# Camera_module.net
KiCad netlist of a schematic drawn in Altium Designer
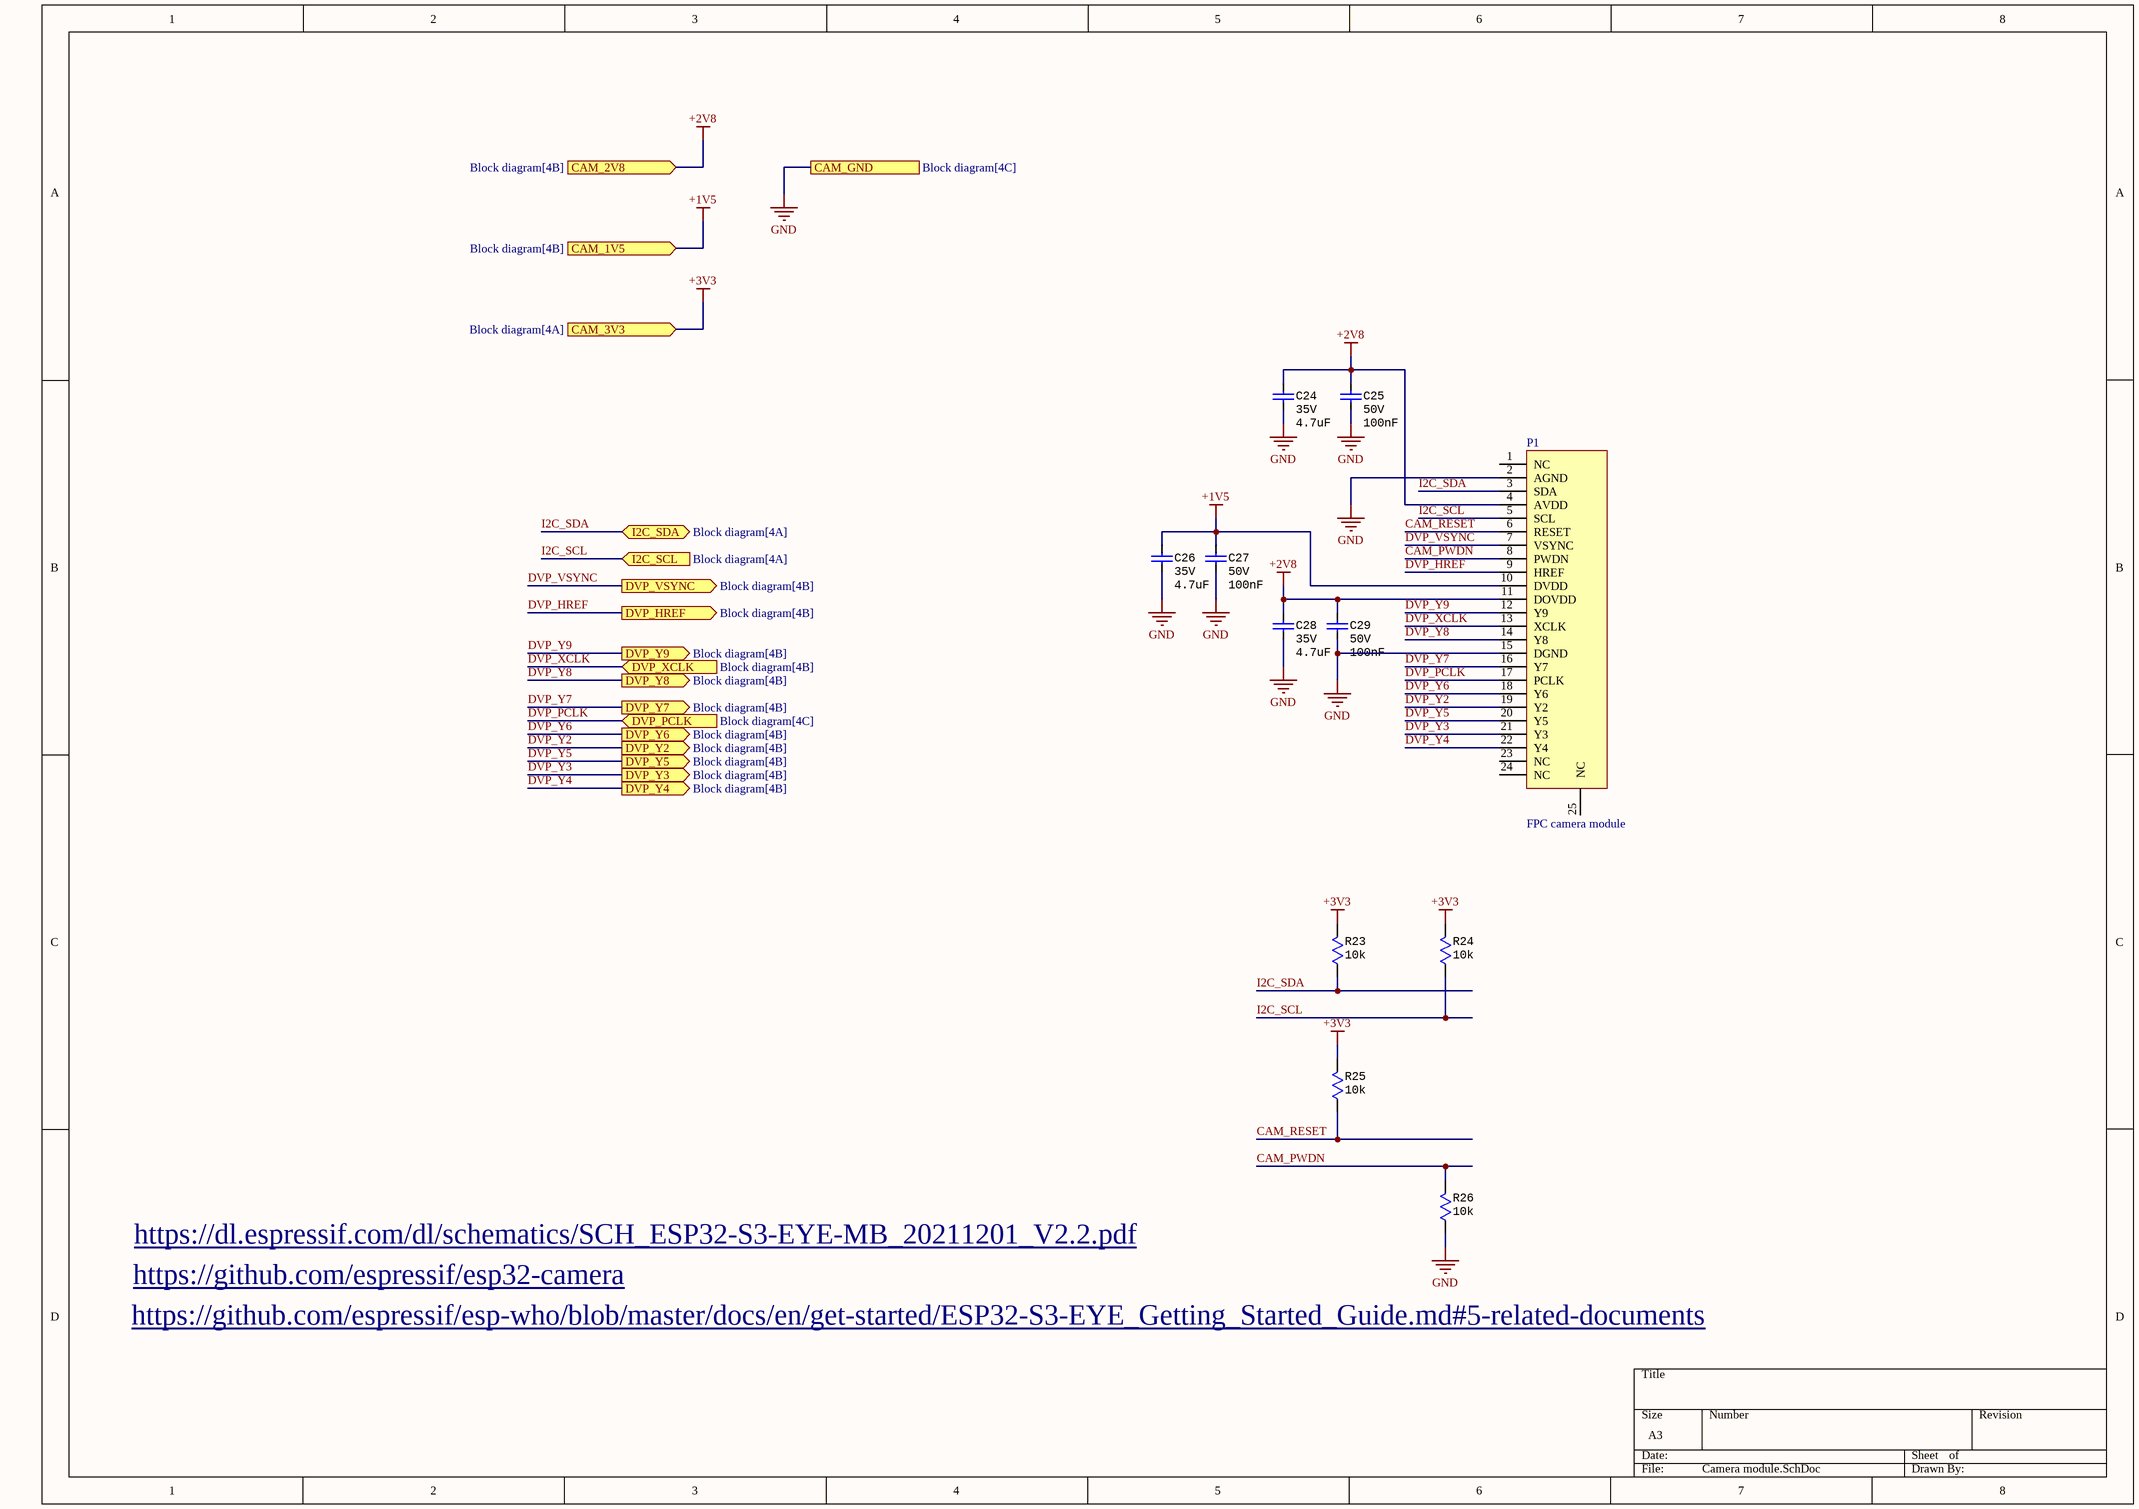
[diagram p0: Camera module.SchDoc]

(export (version "E")
  (design (tool "Eeschema 10.0.6"))
  (components
    (comp (ref "C24")
      (value "4.7uF")
      (footprint "CAP Ceramic SMD 0603")
      (description "Multilayer Ceramic Capacitor, 4.7 uF, 35 V, ± 10%, X5R, 0603 [1608 Metric]")
      (fields
        (field (name "MANUFACTURER") "Murata")
        (field (name "MANUFACTURER PART NUMBER") "GRM188R6YA475KE15D")
        (field (name "VOLTAGE") "35V")
      )
      (libsource (lib "Passive") (part "CAP 0603 4.7uF 35V"))
    )
    (comp (ref "C25")
      (value "100nF")
      (footprint "CAP Ceramic SMD 0603")
      (description "Multilayer Ceramic Capacitors MLCC Surface Mount 0603 0.1uF 50 Volts X7R 10%")
      (fields
        (field (name "MANUFACTURER") "Murata")
        (field (name "MANUFACTURER PART NUMBER") "GRM188R71H104KA93D")
        (field (name "VOLTAGE") "50V")
      )
      (libsource (lib "Passive") (part "CAP 0603 100nF 50V"))
    )
    (comp (ref "C26")
      (value "4.7uF")
      (footprint "CAP Ceramic SMD 0603")
      (description "Multilayer Ceramic Capacitor, 4.7 uF, 35 V, ± 10%, X5R, 0603 [1608 Metric]")
      (fields
        (field (name "MANUFACTURER") "Murata")
        (field (name "MANUFACTURER PART NUMBER") "GRM188R6YA475KE15D")
        (field (name "VOLTAGE") "35V")
      )
      (libsource (lib "Passive") (part "CAP 0603 4.7uF 35V"))
    )
    (comp (ref "C27")
      (value "100nF")
      (footprint "CAP Ceramic SMD 0603")
      (description "Multilayer Ceramic Capacitors MLCC Surface Mount 0603 0.1uF 50 Volts X7R 10%")
      (fields
        (field (name "MANUFACTURER") "Murata")
        (field (name "MANUFACTURER PART NUMBER") "GRM188R71H104KA93D")
        (field (name "VOLTAGE") "50V")
      )
      (libsource (lib "Passive") (part "CAP 0603 100nF 50V"))
    )
    (comp (ref "C28")
      (value "4.7uF")
      (footprint "CAP Ceramic SMD 0603")
      (description "Multilayer Ceramic Capacitor, 4.7 uF, 35 V, ± 10%, X5R, 0603 [1608 Metric]")
      (fields
        (field (name "MANUFACTURER") "Murata")
        (field (name "MANUFACTURER PART NUMBER") "GRM188R6YA475KE15D")
        (field (name "VOLTAGE") "35V")
      )
      (libsource (lib "Passive") (part "CAP 0603 4.7uF 35V"))
    )
    (comp (ref "C29")
      (value "100nF")
      (footprint "CAP Ceramic SMD 0603")
      (description "Multilayer Ceramic Capacitors MLCC Surface Mount 0603 0.1uF 50 Volts X7R 10%")
      (fields
        (field (name "MANUFACTURER") "Murata")
        (field (name "MANUFACTURER PART NUMBER") "GRM188R71H104KA93D")
        (field (name "VOLTAGE") "50V")
      )
      (libsource (lib "Passive") (part "CAP 0603 100nF 50V"))
    )
    (comp (ref "P1")
      (value "FPC camera module")
      (footprint "FPC24 Camera Module")
      (fields
        (field (name "MANUFACTURER") "JUSHUO")
        (field (name "MANUFACTURERPARTNUMBER") "AFC01-S24FCA-00")
      )
      (libsource (lib "Modules") (part "FPC camera module"))
    )
    (comp (ref "R23")
      (value "10k")
      (footprint "RES SMD 0603")
      (description "Res Thick Film 0603 10K Ohm 1% 1/10W ±100ppm/°C Molded SMD Punched Carrier T/R")
      (fields
        (field (name "MANUFACTURER") "Panasonic")
        (field (name "MANUFACTURER PART NUMBER") "ERJ-3EKF1002V")
      )
      (libsource (lib "Passive") (part "RES 0603 10k 1%"))
    )
    (comp (ref "R24")
      (value "10k")
      (footprint "RES SMD 0603")
      (description "Res Thick Film 0603 10K Ohm 1% 1/10W ±100ppm/°C Molded SMD Punched Carrier T/R")
      (fields
        (field (name "MANUFACTURER") "Panasonic")
        (field (name "MANUFACTURER PART NUMBER") "ERJ-3EKF1002V")
      )
      (libsource (lib "Passive") (part "RES 0603 10k 1%"))
    )
    (comp (ref "R25")
      (value "10k")
      (footprint "RES SMD 0603")
      (description "Res Thick Film 0603 10K Ohm 1% 1/10W ±100ppm/°C Molded SMD Punched Carrier T/R")
      (fields
        (field (name "MANUFACTURER") "Panasonic")
        (field (name "MANUFACTURER PART NUMBER") "ERJ-3EKF1002V")
      )
      (libsource (lib "Passive") (part "RES 0603 10k 1%"))
    )
    (comp (ref "R26")
      (value "10k")
      (footprint "RES SMD 0603")
      (description "Res Thick Film 0603 10K Ohm 1% 1/10W ±100ppm/°C Molded SMD Punched Carrier T/R")
      (fields
        (field (name "MANUFACTURER") "Panasonic")
        (field (name "MANUFACTURER PART NUMBER") "ERJ-3EKF1002V")
      )
      (libsource (lib "Passive") (part "RES 0603 10k 1%"))
    )
  )
  (nets
    (net (code "1") (name "+1V5") (class "Default")
      (node (ref "C26") (pin "1") (pinfunction "1_1") (pintype "passive"))
      (node (ref "C27") (pin "1") (pinfunction "1_1") (pintype "passive"))
      (node (ref "P1") (pin "10") (pinfunction "DVDD_10") (pintype "passive"))
    )
    (net (code "2") (name "+2V8") (class "Default")
      (node (ref "C24") (pin "1") (pinfunction "1_1") (pintype "passive"))
      (node (ref "C25") (pin "1") (pinfunction "1_1") (pintype "passive"))
      (node (ref "C28") (pin "1") (pinfunction "1_1") (pintype "passive"))
      (node (ref "C29") (pin "1") (pinfunction "1_1") (pintype "passive"))
      (node (ref "P1") (pin "11") (pinfunction "DOVDD_11") (pintype "passive"))
      (node (ref "P1") (pin "4") (pinfunction "AVDD_4") (pintype "passive"))
    )
    (net (code "3") (name "+3V3") (class "Default")
      (node (ref "R23") (pin "2") (pinfunction "2_2") (pintype "passive"))
      (node (ref "R24") (pin "2") (pinfunction "2_2") (pintype "passive"))
      (node (ref "R25") (pin "2") (pinfunction "2_2") (pintype "passive"))
    )
    (net (code "4") (name "/CAM_PWDN") (class "Default")
      (node (ref "P1") (pin "8") (pinfunction "PWDN_8") (pintype "passive"))
      (node (ref "R26") (pin "2") (pinfunction "2_2") (pintype "passive"))
    )
    (net (code "5") (name "/CAM_RESET") (class "Default")
      (node (ref "P1") (pin "6") (pinfunction "RESET_6") (pintype "passive"))
      (node (ref "R25") (pin "1") (pinfunction "1_1") (pintype "passive"))
    )
    (net (code "6") (name "/DVP_HREF") (class "Default")
      (node (ref "P1") (pin "9") (pinfunction "HREF_9") (pintype "passive"))
    )
    (net (code "7") (name "/DVP_PCLK") (class "Default")
      (node (ref "P1") (pin "17") (pinfunction "PCLK_17") (pintype "passive"))
    )
    (net (code "8") (name "/DVP_VSYNC") (class "Default")
      (node (ref "P1") (pin "7") (pinfunction "VSYNC_7") (pintype "passive"))
    )
    (net (code "9") (name "/DVP_XCLK") (class "Default")
      (node (ref "P1") (pin "13") (pinfunction "XCLK_13") (pintype "passive"))
    )
    (net (code "10") (name "/DVP_Y2") (class "Default")
      (node (ref "P1") (pin "19") (pinfunction "Y2_19") (pintype "passive"))
    )
    (net (code "11") (name "/DVP_Y3") (class "Default")
      (node (ref "P1") (pin "21") (pinfunction "Y3_21") (pintype "passive"))
    )
    (net (code "12") (name "/DVP_Y4") (class "Default")
      (node (ref "P1") (pin "22") (pinfunction "Y4_22") (pintype "passive"))
    )
    (net (code "13") (name "/DVP_Y5") (class "Default")
      (node (ref "P1") (pin "20") (pinfunction "Y5_20") (pintype "passive"))
    )
    (net (code "14") (name "/DVP_Y6") (class "Default")
      (node (ref "P1") (pin "18") (pinfunction "Y6_18") (pintype "passive"))
    )
    (net (code "15") (name "/DVP_Y7") (class "Default")
      (node (ref "P1") (pin "16") (pinfunction "Y7_16") (pintype "passive"))
    )
    (net (code "16") (name "/DVP_Y8") (class "Default")
      (node (ref "P1") (pin "14") (pinfunction "Y8_14") (pintype "passive"))
    )
    (net (code "17") (name "/DVP_Y9") (class "Default")
      (node (ref "P1") (pin "12") (pinfunction "Y9_12") (pintype "passive"))
    )
    (net (code "18") (name "/I2C_SCL") (class "Default")
      (node (ref "P1") (pin "5") (pinfunction "SCL_5") (pintype "passive"))
      (node (ref "R24") (pin "1") (pinfunction "1_1") (pintype "passive"))
    )
    (net (code "19") (name "/I2C_SDA") (class "Default")
      (node (ref "P1") (pin "3") (pinfunction "SDA_3") (pintype "passive"))
      (node (ref "R23") (pin "1") (pinfunction "1_1") (pintype "passive"))
    )
    (net (code "20") (name "GND") (class "Default")
      (node (ref "C24") (pin "2") (pinfunction "2_2") (pintype "passive"))
      (node (ref "C25") (pin "2") (pinfunction "2_2") (pintype "passive"))
      (node (ref "C26") (pin "2") (pinfunction "2_2") (pintype "passive"))
      (node (ref "C27") (pin "2") (pinfunction "2_2") (pintype "passive"))
      (node (ref "C28") (pin "2") (pinfunction "2_2") (pintype "passive"))
      (node (ref "C29") (pin "2") (pinfunction "2_2") (pintype "passive"))
      (node (ref "P1") (pin "15") (pinfunction "DGND_15") (pintype "passive"))
      (node (ref "P1") (pin "2") (pinfunction "AGND_2") (pintype "passive"))
      (node (ref "R26") (pin "1") (pinfunction "1_1") (pintype "passive"))
    )
    (net (code "21") (name "unconnected-(P1-NC-Pad1)") (class "Default")
      (node (ref "P1") (pin "1") (pinfunction "NC_1") (pintype "passive"))
    )
    (net (code "22") (name "unconnected-(P1-NC-Pad23)") (class "Default")
      (node (ref "P1") (pin "23") (pinfunction "NC_23") (pintype "passive"))
    )
    (net (code "23") (name "unconnected-(P1-NC-Pad24)") (class "Default")
      (node (ref "P1") (pin "24") (pinfunction "NC_24") (pintype "passive"))
    )
    (net (code "24") (name "unconnected-(P1-NC-Pad25)") (class "Default")
      (node (ref "P1") (pin "25") (pinfunction "NC_25") (pintype "passive"))
    )
  )
)
